# bk-circ7-S.net
KiCad netlist of a schematic drawn in EAGLE
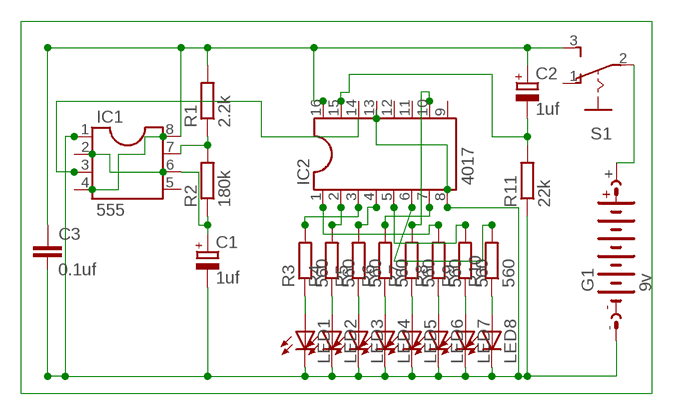
[diagram p0: schematic, sheet 1]

(export (version "E")
  (design (tool "Eeschema 10.0.6"))
  (components
    (comp (ref "C1")
      (value "1uf")
      (footprint "eagle-import:E1,8-4")
      (libsource (lib "eagle-import") (part "CPOL-EUE1.8-4"))
    )
    (comp (ref "C2")
      (value "1uf")
      (footprint "eagle-import:E1,8-4")
      (libsource (lib "eagle-import") (part "CPOL-EUE1.8-4"))
    )
    (comp (ref "C3")
      (value "0.1uf")
      (footprint "eagle-import:C025-024X044")
      (libsource (lib "eagle-import") (part "C-EU025-024X044"))
    )
    (comp (ref "G1")
      (value "9v")
      (footprint "eagle-import:AB9V")
      (libsource (lib "eagle-import") (part "AB9V"))
    )
    (comp (ref "IC1")
      (value "555")
      (footprint "eagle-import:DIL08")
      (libsource (lib "eagle-import") (part "DIL8"))
    )
    (comp (ref "IC2")
      (value "4017")
      (footprint "eagle-import:DIL16")
      (libsource (lib "eagle-import") (part "DIL16"))
    )
    (comp (ref "LED1")
      (value "LED3MM")
      (footprint "eagle-import:LED3MM")
      (libsource (lib "eagle-import") (part "LED3MM"))
    )
    (comp (ref "LED2")
      (value "LED3MM")
      (footprint "eagle-import:LED3MM")
      (libsource (lib "eagle-import") (part "LED3MM"))
    )
    (comp (ref "LED3")
      (value "LED3MM")
      (footprint "eagle-import:LED3MM")
      (libsource (lib "eagle-import") (part "LED3MM"))
    )
    (comp (ref "LED4")
      (value "LED3MM")
      (footprint "eagle-import:LED3MM")
      (libsource (lib "eagle-import") (part "LED3MM"))
    )
    (comp (ref "LED5")
      (value "LED3MM")
      (footprint "eagle-import:LED3MM")
      (libsource (lib "eagle-import") (part "LED3MM"))
    )
    (comp (ref "LED6")
      (value "LED3MM")
      (footprint "eagle-import:LED3MM")
      (libsource (lib "eagle-import") (part "LED3MM"))
    )
    (comp (ref "LED7")
      (value "LED3MM")
      (footprint "eagle-import:LED3MM")
      (libsource (lib "eagle-import") (part "LED3MM"))
    )
    (comp (ref "LED8")
      (value "LED3MM")
      (footprint "eagle-import:LED3MM")
      (libsource (lib "eagle-import") (part "LED3MM"))
    )
    (comp (ref "R1")
      (value "2.2k")
      (footprint "eagle-import:0207_10")
      (libsource (lib "eagle-import") (part "R-EU_0207/10"))
    )
    (comp (ref "R2")
      (value "180k")
      (footprint "eagle-import:0207_10")
      (libsource (lib "eagle-import") (part "R-EU_0207/10"))
    )
    (comp (ref "R3")
      (value "560")
      (footprint "eagle-import:0207_10")
      (libsource (lib "eagle-import") (part "R-EU_0207/10"))
    )
    (comp (ref "R4")
      (value "560")
      (footprint "eagle-import:0207_10")
      (libsource (lib "eagle-import") (part "R-EU_0207/10"))
    )
    (comp (ref "R5")
      (value "560")
      (footprint "eagle-import:0207_10")
      (libsource (lib "eagle-import") (part "R-EU_0207/10"))
    )
    (comp (ref "R6")
      (value "560")
      (footprint "eagle-import:0207_10")
      (libsource (lib "eagle-import") (part "R-EU_0207/10"))
    )
    (comp (ref "R7")
      (value "560")
      (footprint "eagle-import:0207_10")
      (libsource (lib "eagle-import") (part "R-EU_0207/10"))
    )
    (comp (ref "R8")
      (value "560")
      (footprint "eagle-import:0207_10")
      (libsource (lib "eagle-import") (part "R-EU_0207/10"))
    )
    (comp (ref "R9")
      (value "560")
      (footprint "eagle-import:0207_10")
      (libsource (lib "eagle-import") (part "R-EU_0207/10"))
    )
    (comp (ref "R10")
      (value "560")
      (footprint "eagle-import:0207_10")
      (libsource (lib "eagle-import") (part "R-EU_0207/10"))
    )
    (comp (ref "R11")
      (value "22k")
      (footprint "eagle-import:0207_10")
      (libsource (lib "eagle-import") (part "R-EU_0207/10"))
    )
    (comp (ref "S1")
      (value "255SB")
      (footprint "eagle-import:255SB")
      (libsource (lib "eagle-import") (part "255SB"))
    )
  )
  (nets
    (net (code "1") (name "Net-(C1-Pad+)") (class "Default")
      (node (ref "C1") (pin "+") (pinfunction "+_+") (pintype "passive"))
      (node (ref "IC1") (pin "6") (pinfunction "6_6") (pintype "passive"))
      (node (ref "R2") (pin "1") (pinfunction "1_1") (pintype "passive"))
    )
    (net (code "2") (name "Net-(C2-Pad-)") (class "Default")
      (node (ref "C2") (pin "-") (pinfunction "-_-") (pintype "passive"))
      (node (ref "IC2") (pin "15") (pinfunction "15_15") (pintype "passive"))
      (node (ref "R11") (pin "2") (pinfunction "2_2") (pintype "passive"))
    )
    (net (code "3") (name "Net-(IC1-Pad7)") (class "Default")
      (node (ref "IC1") (pin "7") (pinfunction "7_7") (pintype "passive"))
      (node (ref "R1") (pin "1") (pinfunction "1_1") (pintype "passive"))
      (node (ref "R2") (pin "2") (pinfunction "2_2") (pintype "passive"))
    )
    (net (code "4") (name "Net-(IC2-Pad1)") (class "Default")
      (node (ref "IC2") (pin "1") (pinfunction "1_1") (pintype "passive"))
      (node (ref "R8") (pin "2") (pinfunction "2_2") (pintype "passive"))
    )
    (net (code "5") (name "Net-(IC2-Pad2)") (class "Default")
      (node (ref "IC2") (pin "2") (pinfunction "2_2") (pintype "passive"))
      (node (ref "R4") (pin "2") (pinfunction "2_2") (pintype "passive"))
    )
    (net (code "6") (name "Net-(IC2-Pad3)") (class "Default")
      (node (ref "IC2") (pin "3") (pinfunction "3_3") (pintype "passive"))
      (node (ref "R3") (pin "2") (pinfunction "2_2") (pintype "passive"))
    )
    (net (code "7") (name "Net-(IC2-Pad4)") (class "Default")
      (node (ref "IC2") (pin "4") (pinfunction "4_4") (pintype "passive"))
      (node (ref "R5") (pin "2") (pinfunction "2_2") (pintype "passive"))
    )
    (net (code "8") (name "Net-(IC2-Pad5)") (class "Default")
      (node (ref "IC2") (pin "5") (pinfunction "5_5") (pintype "passive"))
      (node (ref "R9") (pin "2") (pinfunction "2_2") (pintype "passive"))
    )
    (net (code "9") (name "Net-(IC2-Pad6)") (class "Default")
      (node (ref "IC2") (pin "6") (pinfunction "6_6") (pintype "passive"))
      (node (ref "R10") (pin "2") (pinfunction "2_2") (pintype "passive"))
    )
    (net (code "10") (name "Net-(IC2-Pad7)") (class "Default")
      (node (ref "IC2") (pin "7") (pinfunction "7_7") (pintype "passive"))
      (node (ref "R6") (pin "2") (pinfunction "2_2") (pintype "passive"))
    )
    (net (code "11") (name "Net-(IC2-Pad10)") (class "Default")
      (node (ref "IC2") (pin "10") (pinfunction "10_10") (pintype "passive"))
      (node (ref "R7") (pin "2") (pinfunction "2_2") (pintype "passive"))
    )
    (net (code "12") (name "Net-(LED1-C)") (class "Default")
      (node (ref "C1") (pin "-") (pinfunction "-_-") (pintype "passive"))
      (node (ref "C3") (pin "2") (pinfunction "2_2") (pintype "passive"))
      (node (ref "G1") (pin "-") (pinfunction "-_-") (pintype "passive"))
      (node (ref "IC1") (pin "1") (pinfunction "1_1") (pintype "passive"))
      (node (ref "IC2") (pin "8") (pinfunction "8_8") (pintype "passive"))
      (node (ref "LED1") (pin "K") (pinfunction "C_K") (pintype "passive"))
      (node (ref "LED2") (pin "K") (pinfunction "C_K") (pintype "passive"))
      (node (ref "LED3") (pin "K") (pinfunction "C_K") (pintype "passive"))
      (node (ref "LED4") (pin "K") (pinfunction "C_K") (pintype "passive"))
      (node (ref "LED5") (pin "K") (pinfunction "C_K") (pintype "passive"))
      (node (ref "LED6") (pin "K") (pinfunction "C_K") (pintype "passive"))
      (node (ref "LED7") (pin "K") (pinfunction "C_K") (pintype "passive"))
      (node (ref "LED8") (pin "K") (pinfunction "C_K") (pintype "passive"))
      (node (ref "R11") (pin "1") (pinfunction "1_1") (pintype "passive"))
    )
    (net (code "13") (name "Net-(LED1-PadA)") (class "Default")
      (node (ref "LED1") (pin "A") (pinfunction "A_A") (pintype "passive"))
      (node (ref "R3") (pin "1") (pinfunction "1_1") (pintype "passive"))
    )
    (net (code "14") (name "Net-(LED2-PadA)") (class "Default")
      (node (ref "LED2") (pin "A") (pinfunction "A_A") (pintype "passive"))
      (node (ref "R4") (pin "1") (pinfunction "1_1") (pintype "passive"))
    )
    (net (code "15") (name "Net-(LED3-PadA)") (class "Default")
      (node (ref "LED3") (pin "A") (pinfunction "A_A") (pintype "passive"))
      (node (ref "R5") (pin "1") (pinfunction "1_1") (pintype "passive"))
    )
    (net (code "16") (name "Net-(LED4-PadA)") (class "Default")
      (node (ref "LED4") (pin "A") (pinfunction "A_A") (pintype "passive"))
      (node (ref "R6") (pin "1") (pinfunction "1_1") (pintype "passive"))
    )
    (net (code "17") (name "Net-(LED5-PadA)") (class "Default")
      (node (ref "LED5") (pin "A") (pinfunction "A_A") (pintype "passive"))
      (node (ref "R7") (pin "1") (pinfunction "1_1") (pintype "passive"))
    )
    (net (code "18") (name "Net-(LED6-PadA)") (class "Default")
      (node (ref "LED6") (pin "A") (pinfunction "A_A") (pintype "passive"))
      (node (ref "R8") (pin "1") (pinfunction "1_1") (pintype "passive"))
    )
    (net (code "19") (name "Net-(LED7-PadA)") (class "Default")
      (node (ref "LED7") (pin "A") (pinfunction "A_A") (pintype "passive"))
      (node (ref "R9") (pin "1") (pinfunction "1_1") (pintype "passive"))
    )
    (net (code "20") (name "Net-(LED8-PadA)") (class "Default")
      (node (ref "LED8") (pin "A") (pinfunction "A_A") (pintype "passive"))
      (node (ref "R10") (pin "1") (pinfunction "1_1") (pintype "passive"))
    )
    (net (code "21") (name "Net-(S1-P)") (class "Default")
      (node (ref "G1") (pin "+") (pinfunction "+_+") (pintype "passive"))
      (node (ref "S1") (pin "2") (pinfunction "P_2") (pintype "passive"))
    )
    (net (code "22") (name "Net-(S1-S)") (class "Default")
      (node (ref "C2") (pin "+") (pinfunction "+_+") (pintype "passive"))
      (node (ref "C3") (pin "1") (pinfunction "1_1") (pintype "passive"))
      (node (ref "IC1") (pin "8") (pinfunction "8_8") (pintype "passive"))
      (node (ref "IC2") (pin "16") (pinfunction "16_16") (pintype "passive"))
      (node (ref "R1") (pin "2") (pinfunction "2_2") (pintype "passive"))
      (node (ref "S1") (pin "3") (pinfunction "S_3") (pintype "passive"))
    )
    (net (code "23") (name "unconnected-(IC1-Pad2)") (class "Default")
      (node (ref "IC1") (pin "2") (pinfunction "2_2") (pintype "passive"))
    )
    (net (code "24") (name "unconnected-(IC1-Pad3)") (class "Default")
      (node (ref "IC1") (pin "3") (pinfunction "3_3") (pintype "passive"))
    )
    (net (code "25") (name "unconnected-(IC1-Pad4)") (class "Default")
      (node (ref "IC1") (pin "4") (pinfunction "4_4") (pintype "passive"))
    )
    (net (code "26") (name "unconnected-(IC1-Pad5)") (class "Default")
      (node (ref "IC1") (pin "5") (pinfunction "5_5") (pintype "passive"))
    )
    (net (code "27") (name "unconnected-(IC2-Pad9)") (class "Default")
      (node (ref "IC2") (pin "9") (pinfunction "9_9") (pintype "passive"))
    )
    (net (code "28") (name "unconnected-(IC2-Pad11)") (class "Default")
      (node (ref "IC2") (pin "11") (pinfunction "11_11") (pintype "passive"))
    )
    (net (code "29") (name "unconnected-(IC2-Pad12)") (class "Default")
      (node (ref "IC2") (pin "12") (pinfunction "12_12") (pintype "passive"))
    )
    (net (code "30") (name "unconnected-(IC2-Pad13)") (class "Default")
      (node (ref "IC2") (pin "13") (pinfunction "13_13") (pintype "passive"))
    )
    (net (code "31") (name "unconnected-(IC2-Pad14)") (class "Default")
      (node (ref "IC2") (pin "14") (pinfunction "14_14") (pintype "passive"))
    )
    (net (code "32") (name "unconnected-(S1-O-Pad1)") (class "Default")
      (node (ref "S1") (pin "1") (pinfunction "O_1") (pintype "passive"))
    )
  )
)
